# Relays.net
KiCad netlist of a schematic drawn in Altium Designer
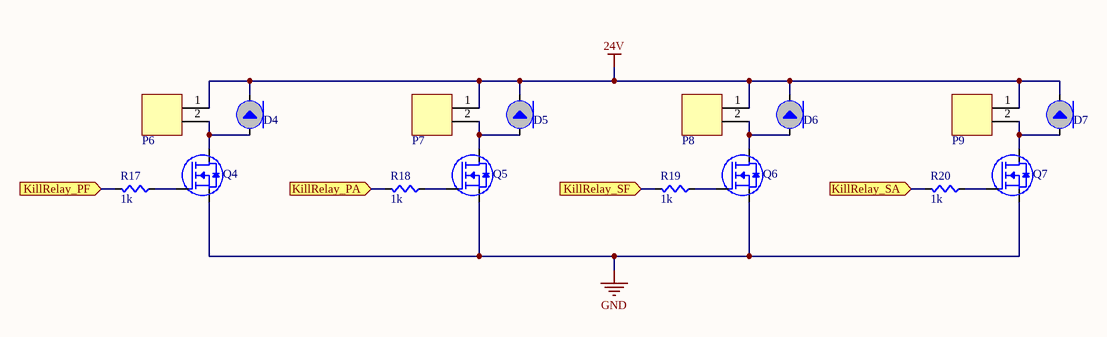
[diagram p0: Relays.SchDoc]

(export (version "E")
  (design (tool "Eeschema 10.0.6"))
  (components
    (comp (ref "D4")
      (value "S1B-13-F")
      (footprint "Semiconductors:SMASeries")
      (description "Standard Diode Template")
      (libsource (lib "Semiconductors") (part "Diode"))
    )
    (comp (ref "D5")
      (value "S1B-13-F")
      (footprint "Semiconductors:SMASeries")
      (description "Standard Diode Template")
      (libsource (lib "Semiconductors") (part "Diode"))
    )
    (comp (ref "D6")
      (value "S1B-13-F")
      (footprint "Semiconductors:SMASeries")
      (description "Standard Diode Template")
      (libsource (lib "Semiconductors") (part "Diode"))
    )
    (comp (ref "D7")
      (value "S1B-13-F")
      (footprint "Semiconductors:SMASeries")
      (description "Standard Diode Template")
      (libsource (lib "Semiconductors") (part "Diode"))
    )
    (comp (ref "P6")
      (value "2-pin Horz Sherlock")
      (footprint "MOLEX-HDR-1X2-SHERLOCK-HORZ")
      (fields
        (field (name "MANUFACTURER PART NUMBER") "0353630260")
        (field (name "MANUFACTURER") "Molex Inc")
      )
      (libsource (lib "Connectors") (part "MOLEX-HDR-1x2-SHERLOCK_RA"))
    )
    (comp (ref "P7")
      (value "2-pin Horz Sherlock")
      (footprint "MOLEX-HDR-1X2-SHERLOCK-HORZ")
      (fields
        (field (name "MANUFACTURER PART NUMBER") "0353630260")
        (field (name "MANUFACTURER") "Molex Inc")
      )
      (libsource (lib "Connectors") (part "MOLEX-HDR-1x2-SHERLOCK_RA"))
    )
    (comp (ref "P8")
      (value "2-pin Horz Sherlock")
      (footprint "MOLEX-HDR-1X2-SHERLOCK-HORZ")
      (fields
        (field (name "MANUFACTURER PART NUMBER") "0353630260")
        (field (name "MANUFACTURER") "Molex Inc")
      )
      (libsource (lib "Connectors") (part "MOLEX-HDR-1x2-SHERLOCK_RA"))
    )
    (comp (ref "P9")
      (value "2-pin Horz Sherlock")
      (footprint "MOLEX-HDR-1X2-SHERLOCK-HORZ")
      (fields
        (field (name "MANUFACTURER PART NUMBER") "0353630260")
        (field (name "MANUFACTURER") "Molex Inc")
      )
      (libsource (lib "Connectors") (part "MOLEX-HDR-1x2-SHERLOCK_RA"))
    )
    (comp (ref "Q4")
      (value "BSN20-7")
      (footprint "Semiconductors:SOT-323")
      (description "NMOSFET Template")
      (libsource (lib "Semiconductors") (part "NMOSFET"))
    )
    (comp (ref "Q5")
      (value "BSN20-7")
      (footprint "Semiconductors:SOT-323")
      (description "NMOSFET Template")
      (libsource (lib "Semiconductors") (part "NMOSFET"))
    )
    (comp (ref "Q6")
      (value "BSN20-7")
      (footprint "Semiconductors:SOT-323")
      (description "NMOSFET Template")
      (libsource (lib "Semiconductors") (part "NMOSFET"))
    )
    (comp (ref "Q7")
      (value "BSN20-7")
      (footprint "Semiconductors:SOT-323")
      (description "NMOSFET Template")
      (libsource (lib "Semiconductors") (part "NMOSFET"))
    )
    (comp (ref "R17")
      (value "1k")
      (footprint "RES0603")
      (fields (field (name "Comment") "Res"))
      (libsource (lib "SubjuGator8") (part "Res"))
    )
    (comp (ref "R18")
      (value "1k")
      (footprint "RES0603")
      (fields (field (name "Comment") "Res"))
      (libsource (lib "SubjuGator8") (part "Res"))
    )
    (comp (ref "R19")
      (value "1k")
      (footprint "RES0603")
      (fields (field (name "Comment") "Res"))
      (libsource (lib "SubjuGator8") (part "Res"))
    )
    (comp (ref "R20")
      (value "1k")
      (footprint "RES0603")
      (fields (field (name "Comment") "Res"))
      (libsource (lib "SubjuGator8") (part "Res"))
    )
  )
  (nets
    (net (code "1") (name "/KillRelay_PA") (class "Default")
      (node (ref "R18") (pin "1") (pinfunction "A_1") (pintype "passive"))
    )
    (net (code "2") (name "/KillRelay_PF") (class "Default")
      (node (ref "R17") (pin "1") (pinfunction "A_1") (pintype "passive"))
    )
    (net (code "3") (name "/KillRelay_SA") (class "Default")
      (node (ref "R20") (pin "1") (pinfunction "A_1") (pintype "passive"))
    )
    (net (code "4") (name "/KillRelay_SF") (class "Default")
      (node (ref "R19") (pin "1") (pinfunction "A_1") (pintype "passive"))
    )
    (net (code "5") (name "24V") (class "Default")
      (node (ref "D4") (pin "C") (pinfunction "C_C") (pintype "passive"))
      (node (ref "D5") (pin "C") (pinfunction "C_C") (pintype "passive"))
      (node (ref "D6") (pin "C") (pinfunction "C_C") (pintype "passive"))
      (node (ref "D7") (pin "C") (pinfunction "C_C") (pintype "passive"))
      (node (ref "P6") (pin "1") (pinfunction "1_1") (pintype "passive"))
      (node (ref "P7") (pin "1") (pinfunction "1_1") (pintype "passive"))
      (node (ref "P8") (pin "1") (pinfunction "1_1") (pintype "passive"))
      (node (ref "P9") (pin "1") (pinfunction "1_1") (pintype "passive"))
    )
    (net (code "6") (name "GND") (class "Default")
      (node (ref "Q4") (pin "2") (pinfunction "S_2") (pintype "passive"))
      (node (ref "Q5") (pin "2") (pinfunction "S_2") (pintype "passive"))
      (node (ref "Q6") (pin "2") (pinfunction "S_2") (pintype "passive"))
      (node (ref "Q7") (pin "2") (pinfunction "S_2") (pintype "passive"))
    )
    (net (code "7") (name "Net-(Q4-D)") (class "Default")
      (node (ref "D4") (pin "A") (pinfunction "A_A") (pintype "passive"))
      (node (ref "P6") (pin "2") (pinfunction "2_2") (pintype "passive"))
      (node (ref "Q4") (pin "3") (pinfunction "D_3") (pintype "passive"))
    )
    (net (code "8") (name "Net-(Q4-G)") (class "Default")
      (node (ref "Q4") (pin "1") (pinfunction "G_1") (pintype "passive"))
      (node (ref "R17") (pin "2") (pinfunction "B_2") (pintype "passive"))
    )
    (net (code "9") (name "Net-(Q5-D)") (class "Default")
      (node (ref "D5") (pin "A") (pinfunction "A_A") (pintype "passive"))
      (node (ref "P7") (pin "2") (pinfunction "2_2") (pintype "passive"))
      (node (ref "Q5") (pin "3") (pinfunction "D_3") (pintype "passive"))
    )
    (net (code "10") (name "Net-(Q5-G)") (class "Default")
      (node (ref "Q5") (pin "1") (pinfunction "G_1") (pintype "passive"))
      (node (ref "R18") (pin "2") (pinfunction "B_2") (pintype "passive"))
    )
    (net (code "11") (name "Net-(Q6-D)") (class "Default")
      (node (ref "D6") (pin "A") (pinfunction "A_A") (pintype "passive"))
      (node (ref "P8") (pin "2") (pinfunction "2_2") (pintype "passive"))
      (node (ref "Q6") (pin "3") (pinfunction "D_3") (pintype "passive"))
    )
    (net (code "12") (name "Net-(Q6-G)") (class "Default")
      (node (ref "Q6") (pin "1") (pinfunction "G_1") (pintype "passive"))
      (node (ref "R19") (pin "2") (pinfunction "B_2") (pintype "passive"))
    )
    (net (code "13") (name "Net-(Q7-D)") (class "Default")
      (node (ref "D7") (pin "A") (pinfunction "A_A") (pintype "passive"))
      (node (ref "P9") (pin "2") (pinfunction "2_2") (pintype "passive"))
      (node (ref "Q7") (pin "3") (pinfunction "D_3") (pintype "passive"))
    )
    (net (code "14") (name "Net-(Q7-G)") (class "Default")
      (node (ref "Q7") (pin "1") (pinfunction "G_1") (pintype "passive"))
      (node (ref "R20") (pin "2") (pinfunction "B_2") (pintype "passive"))
    )
  )
)
